# bk-circ6-S.net
KiCad netlist of a schematic drawn in EAGLE
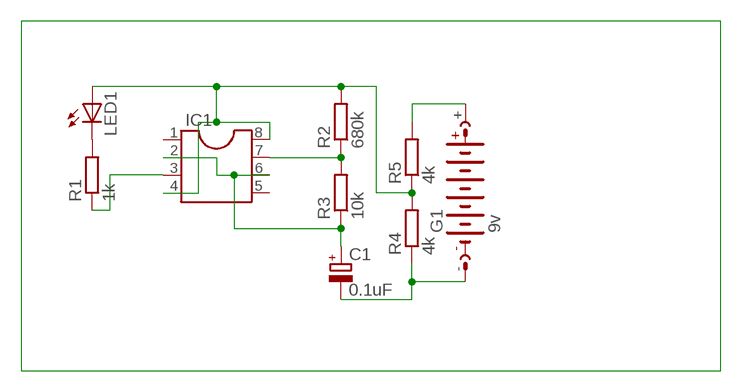
[diagram p0: schematic, sheet 1]

(export (version "E")
  (design (tool "Eeschema 10.0.6"))
  (components
    (comp (ref "C1")
      (value "0.1uF")
      (footprint "eagle-import:B45181B")
      (libsource (lib "eagle-import") (part "CPOL-EUB45181B"))
    )
    (comp (ref "G1")
      (value "9v")
      (footprint "eagle-import:AB9V")
      (libsource (lib "eagle-import") (part "AB9V"))
    )
    (comp (ref "IC1")
      (value "DIL8")
      (footprint "eagle-import:DIL08")
      (libsource (lib "eagle-import") (part "DIL8"))
    )
    (comp (ref "LED1")
      (value "LEDLD260")
      (footprint "eagle-import:LD260")
      (libsource (lib "eagle-import") (part "LEDLD260"))
    )
    (comp (ref "R1")
      (value "1k")
      (footprint "eagle-import:0207_7")
      (libsource (lib "eagle-import") (part "R-EU_0207/7"))
    )
    (comp (ref "R2")
      (value "680k")
      (footprint "eagle-import:0207_7")
      (libsource (lib "eagle-import") (part "R-EU_0207/7"))
    )
    (comp (ref "R3")
      (value "10k")
      (footprint "eagle-import:0207_7")
      (libsource (lib "eagle-import") (part "R-EU_0207/7"))
    )
    (comp (ref "R4")
      (value "4k")
      (footprint "eagle-import:0207_7")
      (libsource (lib "eagle-import") (part "R-EU_0207/7"))
    )
    (comp (ref "R5")
      (value "4k")
      (footprint "eagle-import:0207_7")
      (libsource (lib "eagle-import") (part "R-EU_0207/7"))
    )
  )
  (nets
    (net (code "1") (name "Net-(C1-Pad+)") (class "Default")
      (node (ref "C1") (pin "+") (pinfunction "+_+") (pintype "passive"))
      (node (ref "IC1") (pin "2") (pinfunction "2_2") (pintype "passive"))
      (node (ref "IC1") (pin "6") (pinfunction "6_6") (pintype "passive"))
      (node (ref "R3") (pin "1") (pinfunction "1_1") (pintype "passive"))
    )
    (net (code "2") (name "Net-(C1-Pad-)") (class "Default")
      (node (ref "C1") (pin "-") (pinfunction "-_-") (pintype "passive"))
      (node (ref "G1") (pin "-") (pinfunction "-_-") (pintype "passive"))
      (node (ref "R4") (pin "1") (pinfunction "1_1") (pintype "passive"))
    )
    (net (code "3") (name "Net-(G1-Pad+)") (class "Default")
      (node (ref "G1") (pin "+") (pinfunction "+_+") (pintype "passive"))
      (node (ref "R5") (pin "2") (pinfunction "2_2") (pintype "passive"))
    )
    (net (code "4") (name "Net-(IC1-Pad3)") (class "Default")
      (node (ref "IC1") (pin "3") (pinfunction "3_3") (pintype "passive"))
      (node (ref "R1") (pin "1") (pinfunction "1_1") (pintype "passive"))
    )
    (net (code "5") (name "Net-(IC1-Pad4)") (class "Default")
      (node (ref "IC1") (pin "4") (pinfunction "4_4") (pintype "passive"))
      (node (ref "IC1") (pin "8") (pinfunction "8_8") (pintype "passive"))
      (node (ref "LED1") (pin "A") (pinfunction "A_A") (pintype "passive"))
      (node (ref "R2") (pin "2") (pinfunction "2_2") (pintype "passive"))
      (node (ref "R4") (pin "2") (pinfunction "2_2") (pintype "passive"))
      (node (ref "R5") (pin "1") (pinfunction "1_1") (pintype "passive"))
    )
    (net (code "6") (name "Net-(IC1-Pad7)") (class "Default")
      (node (ref "IC1") (pin "7") (pinfunction "7_7") (pintype "passive"))
      (node (ref "R2") (pin "1") (pinfunction "1_1") (pintype "passive"))
      (node (ref "R3") (pin "2") (pinfunction "2_2") (pintype "passive"))
    )
    (net (code "7") (name "Net-(LED1-C)") (class "Default")
      (node (ref "LED1") (pin "K") (pinfunction "C_K") (pintype "passive"))
      (node (ref "R1") (pin "2") (pinfunction "2_2") (pintype "passive"))
    )
    (net (code "8") (name "unconnected-(IC1-Pad1)") (class "Default")
      (node (ref "IC1") (pin "1") (pinfunction "1_1") (pintype "passive"))
    )
    (net (code "9") (name "unconnected-(IC1-Pad5)") (class "Default")
      (node (ref "IC1") (pin "5") (pinfunction "5_5") (pintype "passive"))
    )
  )
)
